# SCH_connector_V1_0_2024-03-04.net
KiCad netlist of a schematic drawn in EasyEDA
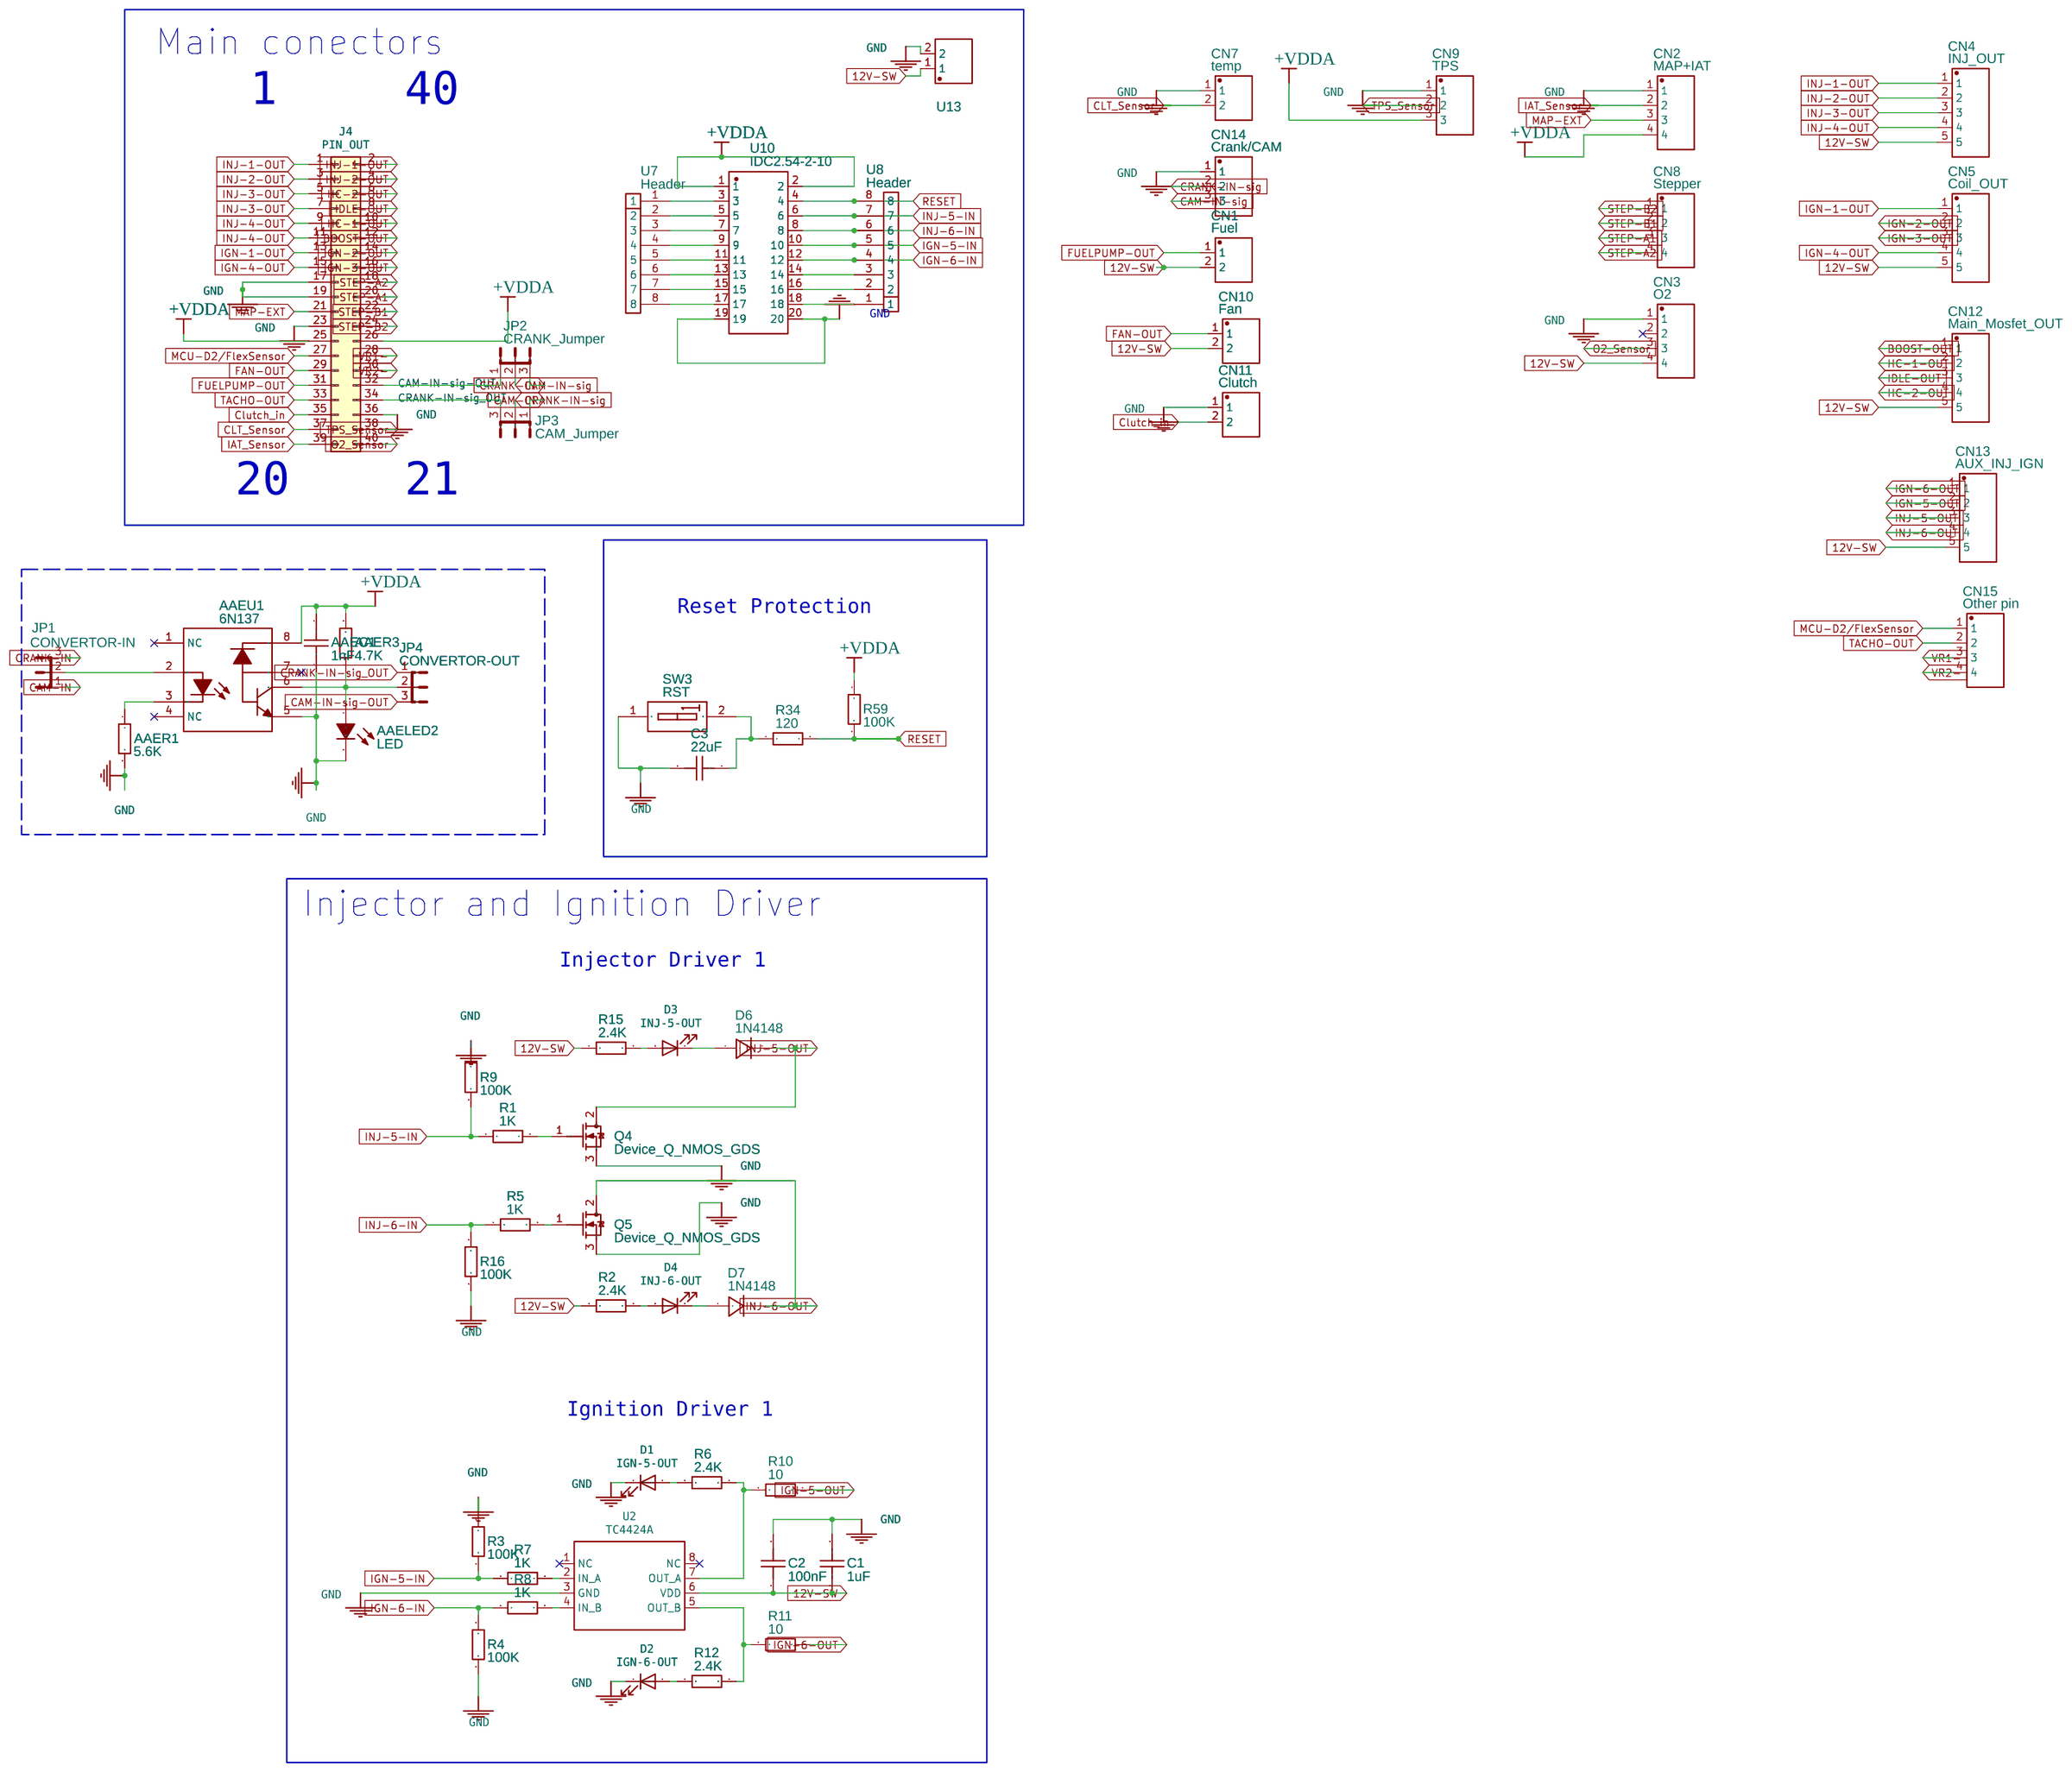
[diagram p0: schematic sheet]

(export (version "E")
  (design (tool "Eeschema 10.0.6"))
  (components
    (comp (ref "AAEC1")
      (value "1nF")
      (fields (field (name "Manufacturer Part") "CC0805KRX7RBBB222") (field (name "Manufacturer") "YAGEO"))
      (libsource (lib "") (part "CC0805KRX7RBBB222"))
    )
    (comp (ref "AAELED2")
      (value "LED")
      (fields
        (field (name "Manufacturer Part") "17-215/G6C-BM1N2L/3T")
        (field (name "Manufacturer") "Everlight Elec")
      )
      (libsource (lib "") (part "17-215/G6C-BM1N2L/3T"))
    )
    (comp (ref "AAER1")
      (value "5.6K")
      (fields (field (name "Manufacturer Part") "RC0805FR-072K74L") (field (name "Manufacturer") "YAGEO"))
      (libsource (lib "") (part "RC0805FR-072K74L_3"))
    )
    (comp (ref "AAER3")
      (value "4.7K")
      (fields (field (name "Manufacturer Part") "RC0805FR-072K74L") (field (name "Manufacturer") "YAGEO"))
      (libsource (lib "") (part "RC0805FR-072K74L_4"))
    )
    (comp (ref "AAEU1")
      (value "6N137")
      (fields (field (name "Manufacturer Part") "6N135") (field (name "Manufacturer") "FAIRCHILD"))
      (libsource (lib "") (part "6N135"))
    )
    (comp (ref "C1")
      (value "1uF")
      (fields (field (name "Manufacturer Part") "08051C105KAT2A") (field (name "Manufacturer") "Kyocera AVX"))
      (libsource (lib "") (part "08051C105KAT2A_1"))
    )
    (comp (ref "C2")
      (value "100nF")
      (fields (field (name "Manufacturer Part") "08051C105KAT2A") (field (name "Manufacturer") "Kyocera AVX"))
      (libsource (lib "") (part "08051C105KAT2A_1"))
    )
    (comp (ref "C3")
      (value "22uF")
      (fields (field (name "Manufacturer Part") "08051C105KAT2A") (field (name "Manufacturer") "Kyocera AVX"))
      (libsource (lib "") (part "08051C105KAT2A"))
    )
    (comp (ref "CN1")
      (value "Fuel")
      (fields (field (name "Manufacturer Part") "PH-12AW") (field (name "Manufacturer") "ReliaPro"))
      (libsource (lib "") (part "PHONIX 2PIN (5.08mm)"))
    )
    (comp (ref "CN2")
      (value "MAP+IAT")
      (fields (field (name "Manufacturer Part") "PH-12AW") (field (name "Manufacturer") "ReliaPro"))
      (libsource (lib "") (part "PHONIX 4PIN (5.08mm)"))
    )
    (comp (ref "CN3")
      (value "O2")
      (fields (field (name "Manufacturer Part") "PH-12AW") (field (name "Manufacturer") "ReliaPro"))
      (libsource (lib "") (part "PHONIX 4PIN (5.08mm)"))
    )
    (comp (ref "CN4")
      (value "INJ_OUT")
      (fields (field (name "Manufacturer Part") "PH-12AW") (field (name "Manufacturer") "ReliaPro"))
      (libsource (lib "") (part "PHONIX 5PIN (5.08mm)"))
    )
    (comp (ref "CN5")
      (value "Coil_OUT")
      (fields (field (name "Manufacturer Part") "PH-12AW") (field (name "Manufacturer") "ReliaPro"))
      (libsource (lib "") (part "PHONIX 5PIN (5.08mm)"))
    )
    (comp (ref "CN7")
      (value "temp")
      (fields (field (name "Manufacturer Part") "PH-12AW") (field (name "Manufacturer") "ReliaPro"))
      (libsource (lib "") (part "PHONIX 2PIN (5.08mm)"))
    )
    (comp (ref "CN8")
      (value "Stepper")
      (fields (field (name "Manufacturer Part") "PH-12AW") (field (name "Manufacturer") "ReliaPro"))
      (libsource (lib "") (part "PHONIX 4PIN (5.08mm)"))
    )
    (comp (ref "CN9")
      (value "TPS")
      (fields (field (name "Manufacturer Part") "PH-12AW") (field (name "Manufacturer") "ReliaPro"))
      (libsource (lib "") (part "PHONIX 3PIN (5.08mm)"))
    )
    (comp (ref "CN10")
      (value "Fan")
      (fields (field (name "Manufacturer Part") "PH-12AW") (field (name "Manufacturer") "ReliaPro"))
      (libsource (lib "") (part "PHONIX 2PIN (5.08mm)"))
    )
    (comp (ref "CN11")
      (value "Clutch")
      (fields (field (name "Manufacturer Part") "PH-12AW") (field (name "Manufacturer") "ReliaPro"))
      (libsource (lib "") (part "PHONIX 2PIN (5.08mm)"))
    )
    (comp (ref "CN12")
      (value "Main_Mosfet_OUT")
      (fields (field (name "Manufacturer Part") "PH-12AW") (field (name "Manufacturer") "ReliaPro"))
      (libsource (lib "") (part "PHONIX 5PIN (5.08mm)"))
    )
    (comp (ref "CN13")
      (value "AUX_INJ_IGN")
      (fields (field (name "Manufacturer Part") "PH-12AW") (field (name "Manufacturer") "ReliaPro"))
      (libsource (lib "") (part "PHONIX 5PIN (5.08mm)"))
    )
    (comp (ref "CN14")
      (value "Crank/CAM")
      (fields (field (name "Manufacturer Part") "PH-12AW") (field (name "Manufacturer") "ReliaPro"))
      (libsource (lib "") (part "PHONIX 3PIN (5.08mm)"))
    )
    (comp (ref "CN15")
      (value "Other pin")
      (fields (field (name "Manufacturer Part") "PH-12AW") (field (name "Manufacturer") "ReliaPro"))
      (libsource (lib "") (part "PHONIX 4PIN (5.08mm)"))
    )
    (comp (ref "D1") (value "IGN-5-OUT") (libsource (lib "") (part "Unknown_-270_1010")))
    (comp (ref "D2") (value "IGN-6-OUT") (libsource (lib "") (part "Unknown_-270_1145")))
    (comp (ref "D3") (value "INJ-5-OUT") (libsource (lib "") (part "Unknown_-255_715")))
    (comp (ref "D4") (value "INJ-6-OUT") (libsource (lib "") (part "Unknown_-255_890")))
    (comp (ref "D6")
      (value "1N4148")
      (fields (field (name "Manufacturer Part") "1N4448HWSQ-7-F") (field (name "Manufacturer") "DIODES(美台)"))
      (libsource (lib "") (part "1N4448HWSQ-7-F"))
    )
    (comp (ref "D7")
      (value "1N4148")
      (fields (field (name "Manufacturer Part") "1N4448HWSQ-7-F") (field (name "Manufacturer") "DIODES(美台)"))
      (libsource (lib "") (part "1N4448HWSQ-7-F"))
    )
    (comp (ref "J4") (value "PIN_OUT") (libsource (lib "") (part "Unknown_-480_205")))
    (comp (ref "JP1") (value "CONVERTOR-IN") (libsource (lib "") (part "JUMPER 3X1 (PIN= 2.54)_2")))
    (comp (ref "JP2") (value "CRANK_Jumper") (libsource (lib "") (part "JUMPER 3X1 (PIN= 2.54)")))
    (comp (ref "JP3") (value "CAM_Jumper") (libsource (lib "") (part "JUMPER 3X1 (PIN= 2.54)_3")))
    (comp (ref "JP4") (value "CONVERTOR-OUT") (libsource (lib "") (part "JUMPER 3X1 (PIN= 2.54)_1")))
    (comp (ref "Q4") (value "Device_Q_NMOS_GDS") (libsource (lib "") (part "Device_Q_NMOS_GDS")))
    (comp (ref "Q5") (value "Device_Q_NMOS_GDS") (libsource (lib "") (part "Device_Q_NMOS_GDS")))
    (comp (ref "R1")
      (value "1K")
      (fields (field (name "Manufacturer Part") "RC0805FR-072K74L") (field (name "Manufacturer") "YAGEO"))
      (libsource (lib "") (part "RC0805FR-072K74L_1"))
    )
    (comp (ref "R2")
      (value "2.4K")
      (fields (field (name "Manufacturer Part") "RC0805FR-072K74L") (field (name "Manufacturer") "YAGEO"))
      (libsource (lib "") (part "RC0805FR-072K74L_1"))
    )
    (comp (ref "R3")
      (value "100K")
      (fields (field (name "Manufacturer Part") "RC0805FR-072K74L") (field (name "Manufacturer") "YAGEO"))
      (libsource (lib "") (part "RC0805FR-072K74L"))
    )
    (comp (ref "R4")
      (value "100K")
      (fields (field (name "Manufacturer Part") "RC0805FR-072K74L") (field (name "Manufacturer") "YAGEO"))
      (libsource (lib "") (part "RC0805FR-072K74L"))
    )
    (comp (ref "R5")
      (value "1K")
      (fields (field (name "Manufacturer Part") "RC0805FR-072K74L") (field (name "Manufacturer") "YAGEO"))
      (libsource (lib "") (part "RC0805FR-072K74L_1"))
    )
    (comp (ref "R6")
      (value "2.4K")
      (fields (field (name "Manufacturer Part") "RC0805FR-072K74L") (field (name "Manufacturer") "YAGEO"))
      (libsource (lib "") (part "RC0805FR-072K74L_1"))
    )
    (comp (ref "R7")
      (value "1K")
      (fields (field (name "Manufacturer Part") "RC0805FR-072K74L") (field (name "Manufacturer") "YAGEO"))
      (libsource (lib "") (part "RC0805FR-072K74L_1"))
    )
    (comp (ref "R8")
      (value "1K")
      (fields (field (name "Manufacturer Part") "RC0805FR-072K74L") (field (name "Manufacturer") "YAGEO"))
      (libsource (lib "") (part "RC0805FR-072K74L_1"))
    )
    (comp (ref "R9")
      (value "100K")
      (fields (field (name "Manufacturer Part") "RC0805FR-072K74L") (field (name "Manufacturer") "YAGEO"))
      (libsource (lib "") (part "RC0805FR-072K74L"))
    )
    (comp (ref "R10")
      (value "10")
      (fields (field (name "Manufacturer Part") "RC0805FR-072K74L") (field (name "Manufacturer") "YAGEO"))
      (libsource (lib "") (part "RC0805FR-072K74L_2"))
    )
    (comp (ref "R11")
      (value "10")
      (fields (field (name "Manufacturer Part") "RC0805FR-072K74L") (field (name "Manufacturer") "YAGEO"))
      (libsource (lib "") (part "RC0805FR-072K74L_2"))
    )
    (comp (ref "R12")
      (value "2.4K")
      (fields (field (name "Manufacturer Part") "RC0805FR-072K74L") (field (name "Manufacturer") "YAGEO"))
      (libsource (lib "") (part "RC0805FR-072K74L_1"))
    )
    (comp (ref "R15")
      (value "2.4K")
      (fields (field (name "Manufacturer Part") "RC0805FR-072K74L") (field (name "Manufacturer") "YAGEO"))
      (libsource (lib "") (part "RC0805FR-072K74L_1"))
    )
    (comp (ref "R16")
      (value "100K")
      (fields (field (name "Manufacturer Part") "RC0805FR-072K74L") (field (name "Manufacturer") "YAGEO"))
      (libsource (lib "") (part "RC0805FR-072K74L"))
    )
    (comp (ref "R34")
      (value "120")
      (fields (field (name "Manufacturer Part") "RC0805FR-072K74L") (field (name "Manufacturer") "YAGEO"))
      (libsource (lib "") (part "RC0805FR-072K74L_1"))
    )
    (comp (ref "R59")
      (value "100K")
      (fields (field (name "Manufacturer Part") "RC0805FR-072K74L") (field (name "Manufacturer") "YAGEO"))
      (libsource (lib "") (part "RC0805FR-072K74L"))
    )
    (comp (ref "SW3")
      (value "RST")
      (fields (field (name "Manufacturer Part") "BDSwitch-2pin-1CH-1r27-SMD-V"))
      (libsource (lib "") (part "BDSWITCH-2PIN-1CH-1R27-SMD-V"))
    )
    (comp (ref "U2") (value "TC4424A") (libsource (lib "") (part "Unknown_-220_1195")))
    (comp (ref "U7")
      (value "Header")
      (fields (field (name "Manufacturer Part") "Male Header 2 pin"))
      (libsource (lib "") (part "1X8 Header (Pin = 2.54)_1"))
    )
    (comp (ref "U8")
      (value "Header")
      (fields (field (name "Manufacturer Part") "Male Header 2 pin"))
      (libsource (lib "") (part "1X8 Header (Pin = 2.54)"))
    )
    (comp (ref "U10")
      (value "IDC2.54-2-10")
      (fields
        (field (name "Manufacturer Part") "ZX-IDC2.54-2-10PZZ")
        (field (name "Manufacturer") "Megastar(兆星)")
      )
      (libsource (lib "") (part "ZX-IDC2.54-2-10PZZ"))
    )
    (comp (ref "U13")
      (value "Power Input")
      (fields (field (name "Manufacturer Part") "PH-12AW") (field (name "Manufacturer") "ReliaPro"))
      (libsource (lib "") (part "PHONIX 2PIN (5.08mm)_1"))
    )
  )
  (nets
    (net (code "1") (name "+VDDA") (class "Default")
      (node (ref "AAEC1") (pin "1") (pinfunction "1_1") (pintype "unspecified"))
      (node (ref "AAER3") (pin "2") (pinfunction "2_2") (pintype "input"))
      (node (ref "AAEU1") (pin "8") (pinfunction "8_8") (pintype "unspecified"))
      (node (ref "CN2") (pin "4") (pinfunction "4_4") (pintype "unspecified"))
      (node (ref "CN9") (pin "3") (pinfunction "3_3") (pintype "unspecified"))
      (node (ref "J4") (pin "25") (pinfunction "Pin_25_25") (pintype "unspecified"))
      (node (ref "J4") (pin "26") (pinfunction "Pin_26_26") (pintype "unspecified"))
      (node (ref "R59") (pin "1") (pinfunction "1_1") (pintype "input"))
      (node (ref "U10") (pin "1") (pinfunction "1_1") (pintype "unspecified"))
      (node (ref "U10") (pin "2") (pinfunction "2_2") (pintype "unspecified"))
    )
    (net (code "2") (name "12V-SW") (class "Default")
      (node (ref "C1") (pin "1") (pinfunction "1_1") (pintype "unspecified"))
      (node (ref "C2") (pin "1") (pinfunction "1_1") (pintype "unspecified"))
      (node (ref "CN1") (pin "2") (pinfunction "2_2") (pintype "unspecified"))
      (node (ref "CN10") (pin "2") (pinfunction "2_2") (pintype "unspecified"))
      (node (ref "CN12") (pin "5") (pinfunction "5_5") (pintype "unspecified"))
      (node (ref "CN13") (pin "5") (pinfunction "5_5") (pintype "unspecified"))
      (node (ref "CN3") (pin "4") (pinfunction "4_4") (pintype "unspecified"))
      (node (ref "CN4") (pin "5") (pinfunction "5_5") (pintype "unspecified"))
      (node (ref "CN5") (pin "5") (pinfunction "5_5") (pintype "unspecified"))
      (node (ref "R15") (pin "1") (pinfunction "1_1") (pintype "input"))
      (node (ref "R2") (pin "1") (pinfunction "1_1") (pintype "input"))
      (node (ref "U13") (pin "1") (pinfunction "1_1") (pintype "unspecified"))
      (node (ref "U2") (pin "6") (pinfunction "VDD_6") (pintype "bidirectional"))
    )
    (net (code "3") (name "BOOST-OUT") (class "Default")
      (node (ref "CN12") (pin "1") (pinfunction "1_1") (pintype "unspecified"))
      (node (ref "J4") (pin "12") (pinfunction "Pin_12_12") (pintype "unspecified"))
    )
    (net (code "4") (name "CAM-IN") (class "Default")
      (node (ref "JP1") (pin "1") (pinfunction "1_1") (pintype "unspecified"))
      (node (ref "JP3") (pin "1") (pinfunction "1_1") (pintype "unspecified"))
    )
    (net (code "5") (name "CAM-IN-sig") (class "Default")
      (node (ref "CN14") (pin "3") (pinfunction "3_3") (pintype "unspecified"))
      (node (ref "JP2") (pin "2") (pinfunction "2_2") (pintype "unspecified"))
    )
    (net (code "6") (name "CAM-IN-sig-OUT") (class "Default")
      (node (ref "J4") (pin "32") (pinfunction "Pin_32_32") (pintype "unspecified"))
      (node (ref "JP2") (pin "1") (pinfunction "1_1") (pintype "unspecified"))
      (node (ref "JP4") (pin "3") (pinfunction "3_3") (pintype "unspecified"))
    )
    (net (code "7") (name "CLT_Sensor") (class "Default")
      (node (ref "CN7") (pin "2") (pinfunction "2_2") (pintype "unspecified"))
      (node (ref "J4") (pin "37") (pinfunction "Pin_37_37") (pintype "unspecified"))
    )
    (net (code "8") (name "CRANK-IN") (class "Default")
      (node (ref "JP1") (pin "3") (pinfunction "3_3") (pintype "unspecified"))
      (node (ref "JP2") (pin "3") (pinfunction "3_3") (pintype "unspecified"))
    )
    (net (code "9") (name "CRANK-IN-sig") (class "Default")
      (node (ref "CN14") (pin "2") (pinfunction "2_2") (pintype "unspecified"))
      (node (ref "JP3") (pin "2") (pinfunction "2_2") (pintype "unspecified"))
    )
    (net (code "10") (name "CRANK-IN-sig_OUT") (class "Default")
      (node (ref "J4") (pin "34") (pinfunction "Pin_34_34") (pintype "unspecified"))
      (node (ref "JP3") (pin "3") (pinfunction "3_3") (pintype "unspecified"))
      (node (ref "JP4") (pin "1") (pinfunction "1_1") (pintype "unspecified"))
    )
    (net (code "11") (name "Clutch_in") (class "Default")
      (node (ref "CN11") (pin "2") (pinfunction "2_2") (pintype "unspecified"))
      (node (ref "J4") (pin "35") (pinfunction "Pin_35_35") (pintype "unspecified"))
    )
    (net (code "12") (name "FAN-OUT") (class "Default")
      (node (ref "CN10") (pin "1") (pinfunction "1_1") (pintype "unspecified"))
      (node (ref "J4") (pin "29") (pinfunction "Pin_29_29") (pintype "unspecified"))
    )
    (net (code "13") (name "FUELPUMP-OUT") (class "Default")
      (node (ref "CN1") (pin "1") (pinfunction "1_1") (pintype "unspecified"))
      (node (ref "J4") (pin "31") (pinfunction "Pin_31_31") (pintype "unspecified"))
    )
    (net (code "14") (name "GND") (class "Default")
      (node (ref "AAEC1") (pin "2") (pinfunction "2_2") (pintype "unspecified"))
      (node (ref "AAELED2") (pin "2") (pinfunction "C_2") (pintype "input"))
      (node (ref "AAER1") (pin "2") (pinfunction "2_2") (pintype "input"))
      (node (ref "AAEU1") (pin "5") (pinfunction "5_5") (pintype "unspecified"))
      (node (ref "C1") (pin "2") (pinfunction "2_2") (pintype "unspecified"))
      (node (ref "C2") (pin "2") (pinfunction "2_2") (pintype "unspecified"))
      (node (ref "C3") (pin "2") (pinfunction "2_2") (pintype "unspecified"))
      (node (ref "CN11") (pin "1") (pinfunction "1_1") (pintype "unspecified"))
      (node (ref "CN14") (pin "1") (pinfunction "1_1") (pintype "unspecified"))
      (node (ref "CN2") (pin "1") (pinfunction "1_1") (pintype "unspecified"))
      (node (ref "CN3") (pin "1") (pinfunction "1_1") (pintype "unspecified"))
      (node (ref "CN7") (pin "1") (pinfunction "1_1") (pintype "unspecified"))
      (node (ref "CN9") (pin "1") (pinfunction "1_1") (pintype "unspecified"))
      (node (ref "D1") (pin "1") (pinfunction "K_1") (pintype "unspecified"))
      (node (ref "D2") (pin "1") (pinfunction "K_1") (pintype "unspecified"))
      (node (ref "J4") (pin "17") (pinfunction "Pin_17_17") (pintype "unspecified"))
      (node (ref "J4") (pin "19") (pinfunction "Pin_19_19") (pintype "unspecified"))
      (node (ref "J4") (pin "23") (pinfunction "Pin_23_23") (pintype "unspecified"))
      (node (ref "J4") (pin "36") (pinfunction "Pin_36_36") (pintype "unspecified"))
      (node (ref "Q4") (pin "3") (pinfunction "S_3") (pintype "unspecified"))
      (node (ref "Q5") (pin "3") (pinfunction "S_3") (pintype "unspecified"))
      (node (ref "R16") (pin "2") (pinfunction "2_2") (pintype "input"))
      (node (ref "R3") (pin "1") (pinfunction "1_1") (pintype "input"))
      (node (ref "R4") (pin "2") (pinfunction "2_2") (pintype "input"))
      (node (ref "R9") (pin "1") (pinfunction "1_1") (pintype "input"))
      (node (ref "SW3") (pin "1") (pinfunction "A1_1") (pintype "input"))
      (node (ref "U10") (pin "19") (pinfunction "19_19") (pintype "unspecified"))
      (node (ref "U10") (pin "20") (pinfunction "20_20") (pintype "unspecified"))
      (node (ref "U13") (pin "2") (pinfunction "2_2") (pintype "unspecified"))
      (node (ref "U2") (pin "3") (pinfunction "GND_3") (pintype "bidirectional"))
    )
    (net (code "15") (name "HC-1-OUT") (class "Default")
      (node (ref "CN12") (pin "2") (pinfunction "2_2") (pintype "unspecified"))
      (node (ref "J4") (pin "10") (pinfunction "Pin_10_10") (pintype "unspecified"))
    )
    (net (code "16") (name "HC-2-OUT") (class "Default")
      (node (ref "CN12") (pin "4") (pinfunction "4_4") (pintype "unspecified"))
      (node (ref "J4") (pin "6") (pinfunction "Pin_6_6") (pintype "unspecified"))
    )
    (net (code "17") (name "IAT_Sensor") (class "Default")
      (node (ref "CN2") (pin "2") (pinfunction "2_2") (pintype "unspecified"))
      (node (ref "J4") (pin "39") (pinfunction "Pin_39_39") (pintype "unspecified"))
    )
    (net (code "18") (name "IDLE-OUT") (class "Default")
      (node (ref "CN12") (pin "3") (pinfunction "3_3") (pintype "unspecified"))
      (node (ref "J4") (pin "8") (pinfunction "Pin_8_8") (pintype "unspecified"))
    )
    (net (code "19") (name "IGN-1-OUT") (class "Default")
      (node (ref "CN5") (pin "1") (pinfunction "1_1") (pintype "unspecified"))
      (node (ref "J4") (pin "13") (pinfunction "Pin_13_13") (pintype "unspecified"))
    )
    (net (code "20") (name "IGN-2-OUT") (class "Default")
      (node (ref "CN5") (pin "2") (pinfunction "2_2") (pintype "unspecified"))
      (node (ref "J4") (pin "14") (pinfunction "Pin_14_14") (pintype "unspecified"))
    )
    (net (code "21") (name "IGN-3-OUT") (class "Default")
      (node (ref "CN5") (pin "3") (pinfunction "3_3") (pintype "unspecified"))
      (node (ref "J4") (pin "16") (pinfunction "Pin_16_16") (pintype "unspecified"))
    )
    (net (code "22") (name "IGN-4-OUT") (class "Default")
      (node (ref "CN5") (pin "4") (pinfunction "4_4") (pintype "unspecified"))
      (node (ref "J4") (pin "15") (pinfunction "Pin_15_15") (pintype "unspecified"))
    )
    (net (code "23") (name "IGN-5-IN") (class "Default")
      (node (ref "R3") (pin "2") (pinfunction "2_2") (pintype "input"))
      (node (ref "R7") (pin "1") (pinfunction "1_1") (pintype "input"))
      (node (ref "U10") (pin "10") (pinfunction "10_10") (pintype "unspecified"))
      (node (ref "U8") (pin "5") (pinfunction "5_5") (pintype "unspecified"))
    )
    (net (code "24") (name "IGN-5-OUT") (class "Default")
      (node (ref "CN13") (pin "2") (pinfunction "2_2") (pintype "unspecified"))
      (node (ref "R10") (pin "1") (pinfunction "1_1") (pintype "input"))
    )
    (net (code "25") (name "IGN-6-IN") (class "Default")
      (node (ref "R4") (pin "1") (pinfunction "1_1") (pintype "input"))
      (node (ref "R8") (pin "1") (pinfunction "1_1") (pintype "input"))
      (node (ref "U10") (pin "12") (pinfunction "12_12") (pintype "unspecified"))
      (node (ref "U8") (pin "4") (pinfunction "4_4") (pintype "unspecified"))
    )
    (net (code "26") (name "IGN-6-OUT") (class "Default")
      (node (ref "CN13") (pin "1") (pinfunction "1_1") (pintype "unspecified"))
      (node (ref "R11") (pin "1") (pinfunction "1_1") (pintype "input"))
    )
    (net (code "27") (name "INJ-1-OUT") (class "Default")
      (node (ref "CN4") (pin "1") (pinfunction "1_1") (pintype "unspecified"))
      (node (ref "J4") (pin "1") (pinfunction "Pin_1_1") (pintype "unspecified"))
      (node (ref "J4") (pin "2") (pinfunction "Pin_2_2") (pintype "unspecified"))
    )
    (net (code "28") (name "INJ-2-OUT") (class "Default")
      (node (ref "CN4") (pin "2") (pinfunction "2_2") (pintype "unspecified"))
      (node (ref "J4") (pin "3") (pinfunction "Pin_3_3") (pintype "unspecified"))
      (node (ref "J4") (pin "4") (pinfunction "Pin_4_4") (pintype "unspecified"))
    )
    (net (code "29") (name "INJ-3-OUT") (class "Default")
      (node (ref "CN4") (pin "3") (pinfunction "3_3") (pintype "unspecified"))
      (node (ref "J4") (pin "5") (pinfunction "Pin_5_5") (pintype "unspecified"))
      (node (ref "J4") (pin "7") (pinfunction "Pin_7_7") (pintype "unspecified"))
    )
    (net (code "30") (name "INJ-4-OUT") (class "Default")
      (node (ref "CN4") (pin "4") (pinfunction "4_4") (pintype "unspecified"))
      (node (ref "J4") (pin "11") (pinfunction "Pin_11_11") (pintype "unspecified"))
      (node (ref "J4") (pin "9") (pinfunction "Pin_9_9") (pintype "unspecified"))
    )
    (net (code "31") (name "INJ-5-IN") (class "Default")
      (node (ref "R1") (pin "1") (pinfunction "1_1") (pintype "input"))
      (node (ref "R9") (pin "2") (pinfunction "2_2") (pintype "input"))
      (node (ref "U10") (pin "6") (pinfunction "6_6") (pintype "unspecified"))
      (node (ref "U8") (pin "7") (pinfunction "7_7") (pintype "unspecified"))
    )
    (net (code "32") (name "INJ-5-OUT") (class "Default")
      (node (ref "CN13") (pin "3") (pinfunction "3_3") (pintype "unspecified"))
      (node (ref "D6") (pin "2") (pinfunction "C_2") (pintype "unspecified"))
      (node (ref "Q4") (pin "2") (pinfunction "D_2") (pintype "unspecified"))
    )
    (net (code "33") (name "INJ-6-IN") (class "Default")
      (node (ref "R16") (pin "1") (pinfunction "1_1") (pintype "input"))
      (node (ref "R5") (pin "1") (pinfunction "1_1") (pintype "input"))
      (node (ref "U10") (pin "8") (pinfunction "8_8") (pintype "unspecified"))
      (node (ref "U8") (pin "6") (pinfunction "6_6") (pintype "unspecified"))
    )
    (net (code "34") (name "INJ-6-OUT") (class "Default")
      (node (ref "CN13") (pin "4") (pinfunction "4_4") (pintype "unspecified"))
      (node (ref "D7") (pin "2") (pinfunction "C_2") (pintype "unspecified"))
      (node (ref "Q5") (pin "2") (pinfunction "D_2") (pintype "unspecified"))
    )
    (net (code "35") (name "MAP-EXT") (class "Default")
      (node (ref "CN2") (pin "3") (pinfunction "3_3") (pintype "unspecified"))
      (node (ref "J4") (pin "21") (pinfunction "Pin_21_21") (pintype "unspecified"))
    )
    (net (code "36") (name "MCU-D2{slash}FlexSensor") (class "Default")
      (node (ref "CN15") (pin "1") (pinfunction "1_1") (pintype "unspecified"))
      (node (ref "J4") (pin "27") (pinfunction "Pin_27_27") (pintype "unspecified"))
    )
    (net (code "37") (name "Net-(AAELED2-A)") (class "Default")
      (node (ref "AAELED2") (pin "1") (pinfunction "A_1") (pintype "input"))
      (node (ref "AAER3") (pin "1") (pinfunction "1_1") (pintype "input"))
      (node (ref "AAEU1") (pin "6") (pinfunction "6_6") (pintype "unspecified"))
      (node (ref "JP4") (pin "2") (pinfunction "2_2") (pintype "unspecified"))
    )
    (net (code "38") (name "Net-(AAER1-Pad1)") (class "Default")
      (node (ref "AAER1") (pin "1") (pinfunction "1_1") (pintype "input"))
      (node (ref "AAEU1") (pin "3") (pinfunction "3_3") (pintype "unspecified"))
    )
    (net (code "39") (name "Net-(AAEU1-Pad2)") (class "Default")
      (node (ref "AAEU1") (pin "2") (pinfunction "2_2") (pintype "unspecified"))
      (node (ref "JP1") (pin "2") (pinfunction "2_2") (pintype "unspecified"))
    )
    (net (code "40") (name "Net-(D1-A)") (class "Default")
      (node (ref "D1") (pin "2") (pinfunction "A_2") (pintype "unspecified"))
      (node (ref "R6") (pin "1") (pinfunction "1_1") (pintype "input"))
    )
    (net (code "41") (name "Net-(D2-A)") (class "Default")
      (node (ref "D2") (pin "2") (pinfunction "A_2") (pintype "unspecified"))
      (node (ref "R12") (pin "1") (pinfunction "1_1") (pintype "input"))
    )
    (net (code "42") (name "Net-(D3-A)") (class "Default")
      (node (ref "D3") (pin "2") (pinfunction "A_2") (pintype "unspecified"))
      (node (ref "R15") (pin "2") (pinfunction "2_2") (pintype "input"))
    )
    (net (code "43") (name "Net-(D3-K)") (class "Default")
      (node (ref "D3") (pin "1") (pinfunction "K_1") (pintype "unspecified"))
      (node (ref "D6") (pin "1") (pinfunction "A_1") (pintype "unspecified"))
    )
    (net (code "44") (name "Net-(D4-A)") (class "Default")
      (node (ref "D4") (pin "2") (pinfunction "A_2") (pintype "unspecified"))
      (node (ref "R2") (pin "2") (pinfunction "2_2") (pintype "input"))
    )
    (net (code "45") (name "Net-(D4-K)") (class "Default")
      (node (ref "D4") (pin "1") (pinfunction "K_1") (pintype "unspecified"))
      (node (ref "D7") (pin "1") (pinfunction "A_1") (pintype "unspecified"))
    )
    (net (code "46") (name "Net-(Q4-G)") (class "Default")
      (node (ref "Q4") (pin "1") (pinfunction "G_1") (pintype "input"))
      (node (ref "R1") (pin "2") (pinfunction "2_2") (pintype "input"))
    )
    (net (code "47") (name "Net-(Q5-G)") (class "Default")
      (node (ref "Q5") (pin "1") (pinfunction "G_1") (pintype "input"))
      (node (ref "R5") (pin "2") (pinfunction "2_2") (pintype "input"))
    )
    (net (code "48") (name "Net-(SW3-B1)") (class "Default")
      (node (ref "C3") (pin "1") (pinfunction "1_1") (pintype "unspecified"))
      (node (ref "R34") (pin "1") (pinfunction "1_1") (pintype "input"))
      (node (ref "SW3") (pin "2") (pinfunction "B1_2") (pintype "input"))
    )
    (net (code "49") (name "Net-(U2-IN_A)") (class "Default")
      (node (ref "R7") (pin "2") (pinfunction "2_2") (pintype "input"))
      (node (ref "U2") (pin "2") (pinfunction "IN_A_2") (pintype "input"))
    )
    (net (code "50") (name "Net-(U2-IN_B)") (class "Default")
      (node (ref "R8") (pin "2") (pinfunction "2_2") (pintype "input"))
      (node (ref "U2") (pin "4") (pinfunction "IN_B_4") (pintype "input"))
    )
    (net (code "51") (name "Net-(U2-OUT_A)") (class "Default")
      (node (ref "R10") (pin "2") (pinfunction "2_2") (pintype "input"))
      (node (ref "R6") (pin "2") (pinfunction "2_2") (pintype "input"))
      (node (ref "U2") (pin "7") (pinfunction "OUT_A_7") (pintype "output"))
    )
    (net (code "52") (name "Net-(U2-OUT_B)") (class "Default")
      (node (ref "R11") (pin "2") (pinfunction "2_2") (pintype "input"))
      (node (ref "R12") (pin "2") (pinfunction "2_2") (pintype "input"))
      (node (ref "U2") (pin "5") (pinfunction "OUT_B_5") (pintype "input"))
    )
    (net (code "53") (name "Net-(U10-Pad3)") (class "Default")
      (node (ref "U10") (pin "3") (pinfunction "3_3") (pintype "unspecified"))
      (node (ref "U7") (pin "1") (pinfunction "1_1") (pintype "unspecified"))
    )
    (net (code "54") (name "Net-(U10-Pad5)") (class "Default")
      (node (ref "U10") (pin "5") (pinfunction "5_5") (pintype "unspecified"))
      (node (ref "U7") (pin "2") (pinfunction "2_2") (pintype "unspecified"))
    )
    (net (code "55") (name "Net-(U10-Pad7)") (class "Default")
      (node (ref "U10") (pin "7") (pinfunction "7_7") (pintype "unspecified"))
      (node (ref "U7") (pin "3") (pinfunction "3_3") (pintype "unspecified"))
    )
    (net (code "56") (name "Net-(U10-Pad9)") (class "Default")
      (node (ref "U10") (pin "9") (pinfunction "9_9") (pintype "unspecified"))
      (node (ref "U7") (pin "4") (pinfunction "4_4") (pintype "unspecified"))
    )
    (net (code "57") (name "Net-(U10-Pad11)") (class "Default")
      (node (ref "U10") (pin "11") (pinfunction "11_11") (pintype "unspecified"))
      (node (ref "U7") (pin "5") (pinfunction "5_5") (pintype "unspecified"))
    )
    (net (code "58") (name "Net-(U10-Pad13)") (class "Default")
      (node (ref "U10") (pin "13") (pinfunction "13_13") (pintype "unspecified"))
      (node (ref "U7") (pin "6") (pinfunction "6_6") (pintype "unspecified"))
    )
    (net (code "59") (name "Net-(U10-Pad14)") (class "Default")
      (node (ref "U10") (pin "14") (pinfunction "14_14") (pintype "unspecified"))
      (node (ref "U8") (pin "3") (pinfunction "3_3") (pintype "unspecified"))
    )
    (net (code "60") (name "Net-(U10-Pad15)") (class "Default")
      (node (ref "U10") (pin "15") (pinfunction "15_15") (pintype "unspecified"))
      (node (ref "U7") (pin "7") (pinfunction "7_7") (pintype "unspecified"))
    )
    (net (code "61") (name "Net-(U10-Pad16)") (class "Default")
      (node (ref "U10") (pin "16") (pinfunction "16_16") (pintype "unspecified"))
      (node (ref "U8") (pin "2") (pinfunction "2_2") (pintype "unspecified"))
    )
    (net (code "62") (name "Net-(U10-Pad17)") (class "Default")
      (node (ref "U10") (pin "17") (pinfunction "17_17") (pintype "unspecified"))
      (node (ref "U7") (pin "8") (pinfunction "8_8") (pintype "unspecified"))
    )
    (net (code "63") (name "Net-(U10-Pad18)") (class "Default")
      (node (ref "U10") (pin "18") (pinfunction "18_18") (pintype "unspecified"))
      (node (ref "U8") (pin "1") (pinfunction "1_1") (pintype "unspecified"))
    )
    (net (code "64") (name "O2_Sensor") (class "Default")
      (node (ref "CN3") (pin "3") (pinfunction "3_3") (pintype "unspecified"))
      (node (ref "J4") (pin "40") (pinfunction "Pin_40_40") (pintype "unspecified"))
    )
    (net (code "65") (name "RESET") (class "Default")
      (node (ref "R34") (pin "2") (pinfunction "2_2") (pintype "input"))
      (node (ref "R59") (pin "2") (pinfunction "2_2") (pintype "input"))
      (node (ref "U10") (pin "4") (pinfunction "4_4") (pintype "unspecified"))
      (node (ref "U8") (pin "8") (pinfunction "8_8") (pintype "unspecified"))
    )
    (net (code "66") (name "STEP-A1") (class "Default")
      (node (ref "CN8") (pin "3") (pinfunction "3_3") (pintype "unspecified"))
      (node (ref "J4") (pin "20") (pinfunction "Pin_20_20") (pintype "unspecified"))
    )
    (net (code "67") (name "STEP-A2") (class "Default")
      (node (ref "CN8") (pin "4") (pinfunction "4_4") (pintype "unspecified"))
      (node (ref "J4") (pin "18") (pinfunction "Pin_18_18") (pintype "unspecified"))
    )
    (net (code "68") (name "STEP-B1") (class "Default")
      (node (ref "CN8") (pin "2") (pinfunction "2_2") (pintype "unspecified"))
      (node (ref "J4") (pin "22") (pinfunction "Pin_22_22") (pintype "unspecified"))
    )
    (net (code "69") (name "STEP-B2") (class "Default")
      (node (ref "CN8") (pin "1") (pinfunction "1_1") (pintype "unspecified"))
      (node (ref "J4") (pin "24") (pinfunction "Pin_24_24") (pintype "unspecified"))
    )
    (net (code "70") (name "TACHO-OUT") (class "Default")
      (node (ref "CN15") (pin "2") (pinfunction "2_2") (pintype "unspecified"))
      (node (ref "J4") (pin "33") (pinfunction "Pin_33_33") (pintype "unspecified"))
    )
    (net (code "71") (name "TPS_Sensor") (class "Default")
      (node (ref "CN9") (pin "2") (pinfunction "2_2") (pintype "unspecified"))
      (node (ref "J4") (pin "38") (pinfunction "Pin_38_38") (pintype "unspecified"))
    )
    (net (code "72") (name "VR1-") (class "Default")
      (node (ref "CN15") (pin "3") (pinfunction "3_3") (pintype "unspecified"))
      (node (ref "J4") (pin "28") (pinfunction "Pin_28_28") (pintype "unspecified"))
    )
    (net (code "73") (name "VR2-") (class "Default")
      (node (ref "CN15") (pin "4") (pinfunction "4_4") (pintype "unspecified"))
      (node (ref "J4") (pin "30") (pinfunction "Pin_30_30") (pintype "unspecified"))
    )
    (net (code "74") (name "unconnected-(AAEU1-NC-Pad1)") (class "Default")
      (node (ref "AAEU1") (pin "1") (pinfunction "NC_1") (pintype "unspecified+no_connect"))
    )
    (net (code "75") (name "unconnected-(AAEU1-NC-Pad4)") (class "Default")
      (node (ref "AAEU1") (pin "4") (pinfunction "NC_4") (pintype "unspecified+no_connect"))
    )
    (net (code "76") (name "unconnected-(AAEU1-Pad7)") (class "Default")
      (node (ref "AAEU1") (pin "7") (pinfunction "7_7") (pintype "unspecified+no_connect"))
    )
    (net (code "77") (name "unconnected-(CN3-Pad2)") (class "Default")
      (node (ref "CN3") (pin "2") (pinfunction "2_2") (pintype "unspecified+no_connect"))
    )
    (net (code "78") (name "unconnected-(U2-NC-Pad1)") (class "Default")
      (node (ref "U2") (pin "1") (pinfunction "NC_1") (pintype "bidirectional+no_connect"))
    )
    (net (code "79") (name "unconnected-(U2-NC-Pad8)") (class "Default")
      (node (ref "U2") (pin "8") (pinfunction "NC_8") (pintype "bidirectional+no_connect"))
    )
  )
)
